# DTImp.net
KiCad netlist of a schematic drawn in Altium Designer
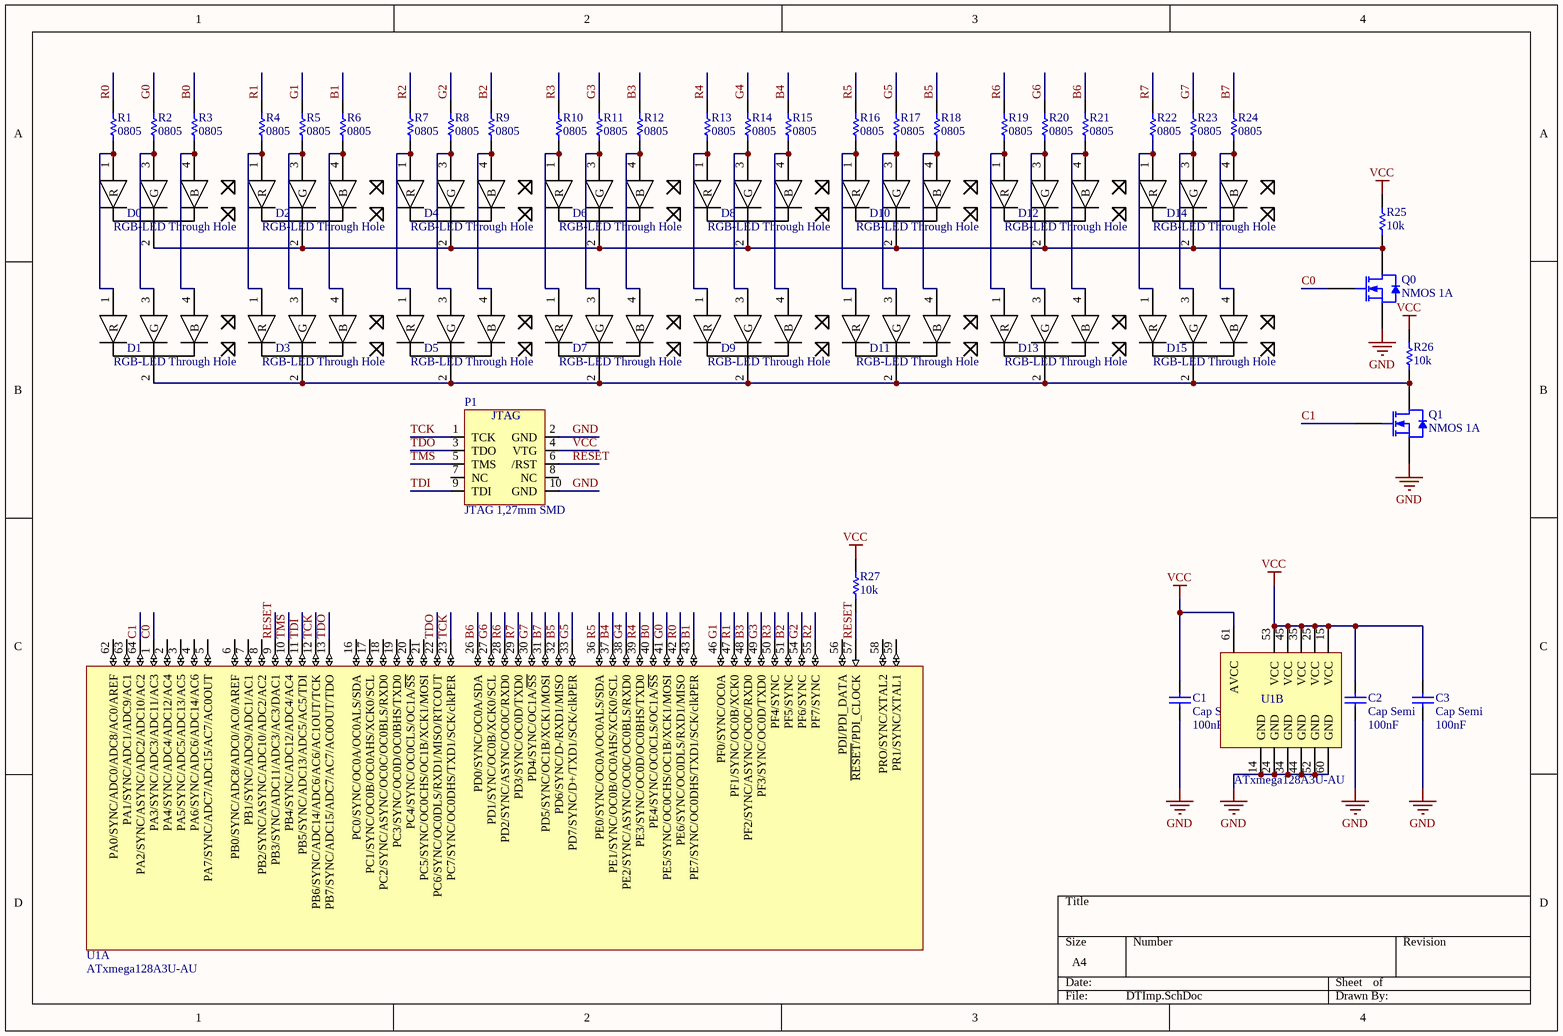
[diagram p0: DTImp.SchDoc]

(export (version "E")
  (design (tool "Eeschema 10.0.6"))
  (components
    (comp (ref "C1")
      (value "Cap Semi")
      (footprint "C1206")
      (description "Capacitor (Semiconductor SIM Model)")
      (fields (field (name "ALTIUM_VALUE") "100nF") (field (name "PUBLISHER") "Altium Limited"))
      (libsource (lib "Miscellaneous Devices") (part "Cap Semi"))
    )
    (comp (ref "C2")
      (value "Cap Semi")
      (footprint "C1206")
      (description "Capacitor (Semiconductor SIM Model)")
      (fields (field (name "ALTIUM_VALUE") "100nF") (field (name "PUBLISHER") "Altium Limited"))
      (libsource (lib "Miscellaneous Devices") (part "Cap Semi"))
    )
    (comp (ref "C3")
      (value "Cap Semi")
      (footprint "C1206")
      (description "Capacitor (Semiconductor SIM Model)")
      (fields (field (name "ALTIUM_VALUE") "100nF") (field (name "PUBLISHER") "Altium Limited"))
      (libsource (lib "Miscellaneous Devices") (part "Cap Semi"))
    )
    (comp (ref "D0")
      (value "RGB-LED Through Hole")
      (footprint "RGB-LED Through Hole")
      (libsource (lib "oystesm") (part "RGB-LED Through Hole"))
    )
    (comp (ref "D1")
      (value "RGB-LED Through Hole")
      (footprint "RGB-LED Through Hole")
      (libsource (lib "oystesm") (part "RGB-LED Through Hole"))
    )
    (comp (ref "D2")
      (value "RGB-LED Through Hole")
      (footprint "RGB-LED Through Hole")
      (libsource (lib "oystesm") (part "RGB-LED Through Hole"))
    )
    (comp (ref "D3")
      (value "RGB-LED Through Hole")
      (footprint "RGB-LED Through Hole")
      (libsource (lib "oystesm") (part "RGB-LED Through Hole"))
    )
    (comp (ref "D4")
      (value "RGB-LED Through Hole")
      (footprint "RGB-LED Through Hole")
      (libsource (lib "oystesm") (part "RGB-LED Through Hole"))
    )
    (comp (ref "D5")
      (value "RGB-LED Through Hole")
      (footprint "RGB-LED Through Hole")
      (libsource (lib "oystesm") (part "RGB-LED Through Hole"))
    )
    (comp (ref "D6")
      (value "RGB-LED Through Hole")
      (footprint "RGB-LED Through Hole")
      (libsource (lib "oystesm") (part "RGB-LED Through Hole"))
    )
    (comp (ref "D7")
      (value "RGB-LED Through Hole")
      (footprint "RGB-LED Through Hole")
      (libsource (lib "oystesm") (part "RGB-LED Through Hole"))
    )
    (comp (ref "D8")
      (value "RGB-LED Through Hole")
      (footprint "RGB-LED Through Hole")
      (libsource (lib "oystesm") (part "RGB-LED Through Hole"))
    )
    (comp (ref "D9")
      (value "RGB-LED Through Hole")
      (footprint "RGB-LED Through Hole")
      (libsource (lib "oystesm") (part "RGB-LED Through Hole"))
    )
    (comp (ref "D10")
      (value "RGB-LED Through Hole")
      (footprint "RGB-LED Through Hole")
      (libsource (lib "oystesm") (part "RGB-LED Through Hole"))
    )
    (comp (ref "D11")
      (value "RGB-LED Through Hole")
      (footprint "RGB-LED Through Hole")
      (libsource (lib "oystesm") (part "RGB-LED Through Hole"))
    )
    (comp (ref "D12")
      (value "RGB-LED Through Hole")
      (footprint "RGB-LED Through Hole")
      (libsource (lib "oystesm") (part "RGB-LED Through Hole"))
    )
    (comp (ref "D13")
      (value "RGB-LED Through Hole")
      (footprint "RGB-LED Through Hole")
      (libsource (lib "oystesm") (part "RGB-LED Through Hole"))
    )
    (comp (ref "D14")
      (value "RGB-LED Through Hole")
      (footprint "RGB-LED Through Hole")
      (libsource (lib "oystesm") (part "RGB-LED Through Hole"))
    )
    (comp (ref "D15")
      (value "RGB-LED Through Hole")
      (footprint "RGB-LED Through Hole")
      (libsource (lib "oystesm") (part "RGB-LED Through Hole"))
    )
    (comp (ref "P1")
      (value "JTAG 1,27mm SMD")
      (footprint "Header 1,27mm SMD 10P")
      (libsource (lib "oystesm") (part "JTAG 1,27mm SMD"))
    )
    (comp (ref "Q0")
      (value "NMOS 1A")
      (footprint "SOT23_N")
      (description "N-channel Enhancement Mode Field-effect Transistor")
      (fields (field (name "PUBLISHER") "Altium Limited"))
      (libsource (lib "Philips Discrete MOSFET - Low Power") (part "2N7002"))
    )
    (comp (ref "Q1")
      (value "NMOS 1A")
      (footprint "SOT23_N")
      (description "N-channel Enhancement Mode Field-effect Transistor")
      (fields (field (name "PUBLISHER") "Altium Limited"))
      (libsource (lib "Philips Discrete MOSFET - Low Power") (part "2N7002"))
    )
    (comp (ref "R1")
      (value "0805")
      (footprint "ERA-0805")
      (description "0805 SMD")
      (fields (field (name "PUBLISHER") "Altium Limited"))
      (libsource (lib "Panasonic Resistor") (part "ERA6Y"))
    )
    (comp (ref "R2")
      (value "0805")
      (footprint "ERA-0805")
      (description "0805 SMD")
      (fields (field (name "PUBLISHER") "Altium Limited"))
      (libsource (lib "Panasonic Resistor") (part "ERA6Y"))
    )
    (comp (ref "R3")
      (value "0805")
      (footprint "ERA-0805")
      (description "0805 SMD")
      (fields (field (name "PUBLISHER") "Altium Limited"))
      (libsource (lib "Panasonic Resistor") (part "ERA6Y"))
    )
    (comp (ref "R4")
      (value "0805")
      (footprint "ERA-0805")
      (description "0805 SMD")
      (fields (field (name "PUBLISHER") "Altium Limited"))
      (libsource (lib "Panasonic Resistor") (part "ERA6Y"))
    )
    (comp (ref "R5")
      (value "0805")
      (footprint "ERA-0805")
      (description "0805 SMD")
      (fields (field (name "PUBLISHER") "Altium Limited"))
      (libsource (lib "Panasonic Resistor") (part "ERA6Y"))
    )
    (comp (ref "R6")
      (value "0805")
      (footprint "ERA-0805")
      (description "0805 SMD")
      (fields (field (name "PUBLISHER") "Altium Limited"))
      (libsource (lib "Panasonic Resistor") (part "ERA6Y"))
    )
    (comp (ref "R7")
      (value "0805")
      (footprint "ERA-0805")
      (description "0805 SMD")
      (fields (field (name "PUBLISHER") "Altium Limited"))
      (libsource (lib "Panasonic Resistor") (part "ERA6Y"))
    )
    (comp (ref "R8")
      (value "0805")
      (footprint "ERA-0805")
      (description "0805 SMD")
      (fields (field (name "PUBLISHER") "Altium Limited"))
      (libsource (lib "Panasonic Resistor") (part "ERA6Y"))
    )
    (comp (ref "R9")
      (value "0805")
      (footprint "ERA-0805")
      (description "0805 SMD")
      (fields (field (name "PUBLISHER") "Altium Limited"))
      (libsource (lib "Panasonic Resistor") (part "ERA6Y"))
    )
    (comp (ref "R10")
      (value "0805")
      (footprint "ERA-0805")
      (description "0805 SMD")
      (fields (field (name "PUBLISHER") "Altium Limited"))
      (libsource (lib "Panasonic Resistor") (part "ERA6Y"))
    )
    (comp (ref "R11")
      (value "0805")
      (footprint "ERA-0805")
      (description "0805 SMD")
      (fields (field (name "PUBLISHER") "Altium Limited"))
      (libsource (lib "Panasonic Resistor") (part "ERA6Y"))
    )
    (comp (ref "R12")
      (value "0805")
      (footprint "ERA-0805")
      (description "0805 SMD")
      (fields (field (name "PUBLISHER") "Altium Limited"))
      (libsource (lib "Panasonic Resistor") (part "ERA6Y"))
    )
    (comp (ref "R13")
      (value "0805")
      (footprint "ERA-0805")
      (description "0805 SMD")
      (fields (field (name "PUBLISHER") "Altium Limited"))
      (libsource (lib "Panasonic Resistor") (part "ERA6Y"))
    )
    (comp (ref "R14")
      (value "0805")
      (footprint "ERA-0805")
      (description "0805 SMD")
      (fields (field (name "PUBLISHER") "Altium Limited"))
      (libsource (lib "Panasonic Resistor") (part "ERA6Y"))
    )
    (comp (ref "R15")
      (value "0805")
      (footprint "ERA-0805")
      (description "0805 SMD")
      (fields (field (name "PUBLISHER") "Altium Limited"))
      (libsource (lib "Panasonic Resistor") (part "ERA6Y"))
    )
    (comp (ref "R16")
      (value "0805")
      (footprint "ERA-0805")
      (description "0805 SMD")
      (fields (field (name "PUBLISHER") "Altium Limited"))
      (libsource (lib "Panasonic Resistor") (part "ERA6Y"))
    )
    (comp (ref "R17")
      (value "0805")
      (footprint "ERA-0805")
      (description "0805 SMD")
      (fields (field (name "PUBLISHER") "Altium Limited"))
      (libsource (lib "Panasonic Resistor") (part "ERA6Y"))
    )
    (comp (ref "R18")
      (value "0805")
      (footprint "ERA-0805")
      (description "0805 SMD")
      (fields (field (name "PUBLISHER") "Altium Limited"))
      (libsource (lib "Panasonic Resistor") (part "ERA6Y"))
    )
    (comp (ref "R19")
      (value "0805")
      (footprint "ERA-0805")
      (description "0805 SMD")
      (fields (field (name "PUBLISHER") "Altium Limited"))
      (libsource (lib "Panasonic Resistor") (part "ERA6Y"))
    )
    (comp (ref "R20")
      (value "0805")
      (footprint "ERA-0805")
      (description "0805 SMD")
      (fields (field (name "PUBLISHER") "Altium Limited"))
      (libsource (lib "Panasonic Resistor") (part "ERA6Y"))
    )
    (comp (ref "R21")
      (value "0805")
      (footprint "ERA-0805")
      (description "0805 SMD")
      (fields (field (name "PUBLISHER") "Altium Limited"))
      (libsource (lib "Panasonic Resistor") (part "ERA6Y"))
    )
    (comp (ref "R22")
      (value "0805")
      (footprint "ERA-0805")
      (description "0805 SMD")
      (fields (field (name "PUBLISHER") "Altium Limited"))
      (libsource (lib "Panasonic Resistor") (part "ERA6Y"))
    )
    (comp (ref "R23")
      (value "0805")
      (footprint "ERA-0805")
      (description "0805 SMD")
      (fields (field (name "PUBLISHER") "Altium Limited"))
      (libsource (lib "Panasonic Resistor") (part "ERA6Y"))
    )
    (comp (ref "R24")
      (value "0805")
      (footprint "ERA-0805")
      (description "0805 SMD")
      (fields (field (name "PUBLISHER") "Altium Limited"))
      (libsource (lib "Panasonic Resistor") (part "ERA6Y"))
    )
    (comp (ref "R25")
      (value "10k")
      (footprint "ERA-0805")
      (fields (field (name "PUBLISHER") "Altium Limited"))
      (libsource (lib "Panasonic Resistor") (part "ERA6Y"))
    )
    (comp (ref "R26")
      (value "10k")
      (footprint "ERA-0805")
      (fields (field (name "PUBLISHER") "Altium Limited"))
      (libsource (lib "Panasonic Resistor") (part "ERA6Y"))
    )
    (comp (ref "R27")
      (value "10k")
      (footprint "ERA-0805")
      (description "10kOhm")
      (fields (field (name "PUBLISHER") "Altium Limited"))
      (libsource (lib "Panasonic Resistor") (part "ERA6Y"))
    )
    (comp (ref "U1")
      (value "ATxmega128A3U-AU")
      (footprint "64A_N")
      (libsource (lib "") (part "ATxmega128A3U-AU_1"))
    )
  )
  (nets
    (net (code "1") (name "/B0") (class "Default")
      (node (ref "R3") (pin "2") (pinfunction "2_2") (pintype "passive"))
      (node (ref "U1") (pin "40") (pinfunction "PE4/SYNC/OC0CLS/OC1A/~{SS}_40") (pintype "bidirectional"))
    )
    (net (code "2") (name "/B1") (class "Default")
      (node (ref "R6") (pin "2") (pinfunction "2_2") (pintype "passive"))
      (node (ref "U1") (pin "43") (pinfunction "PE7/SYNC/OC0DHS/TXD1/SCK/clkPER_43") (pintype "bidirectional"))
    )
    (net (code "3") (name "/B2") (class "Default")
      (node (ref "R9") (pin "2") (pinfunction "2_2") (pintype "passive"))
      (node (ref "U1") (pin "51") (pinfunction "PF5/SYNC_51") (pintype "bidirectional"))
    )
    (net (code "4") (name "/B3") (class "Default")
      (node (ref "R12") (pin "2") (pinfunction "2_2") (pintype "passive"))
      (node (ref "U1") (pin "48") (pinfunction "PF2/SYNC/ASYNC/OC0C/RXD0_48") (pintype "bidirectional"))
    )
    (net (code "5") (name "/B4") (class "Default")
      (node (ref "R15") (pin "2") (pinfunction "2_2") (pintype "passive"))
      (node (ref "U1") (pin "37") (pinfunction "PE1/SYNC/OC0B/OC0AHS/XCK0/SCL_37") (pintype "bidirectional"))
    )
    (net (code "6") (name "/B5") (class "Default")
      (node (ref "R18") (pin "2") (pinfunction "2_2") (pintype "passive"))
      (node (ref "U1") (pin "32") (pinfunction "PD6/SYNC/D-/RXD1/MISO_32") (pintype "bidirectional"))
    )
    (net (code "7") (name "/B6") (class "Default")
      (node (ref "R21") (pin "2") (pinfunction "2_2") (pintype "passive"))
      (node (ref "U1") (pin "26") (pinfunction "PD0/SYNC/OC0A/SDA_26") (pintype "bidirectional"))
    )
    (net (code "8") (name "/B7") (class "Default")
      (node (ref "R24") (pin "2") (pinfunction "2_2") (pintype "passive"))
      (node (ref "U1") (pin "31") (pinfunction "PD5/SYNC/OC1B/XCK1/MOSI_31") (pintype "bidirectional"))
    )
    (net (code "9") (name "/C0") (class "Default")
      (node (ref "Q0") (pin "1") (pinfunction "G_1") (pintype "passive"))
      (node (ref "U1") (pin "1") (pinfunction "PA3/SYNC/ADC3/ADC11/AC3_1") (pintype "bidirectional"))
    )
    (net (code "10") (name "/C1") (class "Default")
      (node (ref "Q1") (pin "1") (pinfunction "G_1") (pintype "passive"))
      (node (ref "U1") (pin "64") (pinfunction "PA2/SYNC/ASYNC/ADC2/ADC10/AC2_64") (pintype "bidirectional"))
    )
    (net (code "11") (name "/G0") (class "Default")
      (node (ref "R2") (pin "2") (pinfunction "2_2") (pintype "passive"))
      (node (ref "U1") (pin "41") (pinfunction "PE5/SYNC/OC0CHS/OC1B/XCK1/MOSI_41") (pintype "bidirectional"))
    )
    (net (code "12") (name "/G1") (class "Default")
      (node (ref "R5") (pin "2") (pinfunction "2_2") (pintype "passive"))
      (node (ref "U1") (pin "46") (pinfunction "PF0/SYNC/OC0A_46") (pintype "bidirectional"))
    )
    (net (code "13") (name "/G2") (class "Default")
      (node (ref "R8") (pin "2") (pinfunction "2_2") (pintype "passive"))
      (node (ref "U1") (pin "54") (pinfunction "PF6/SYNC_54") (pintype "bidirectional"))
    )
    (net (code "14") (name "/G3") (class "Default")
      (node (ref "R11") (pin "2") (pinfunction "2_2") (pintype "passive"))
      (node (ref "U1") (pin "49") (pinfunction "PF3/SYNC/OC0D/TXD0_49") (pintype "bidirectional"))
    )
    (net (code "15") (name "/G4") (class "Default")
      (node (ref "R14") (pin "2") (pinfunction "2_2") (pintype "passive"))
      (node (ref "U1") (pin "38") (pinfunction "PE2/SYNC/ASYNC/OC0C/OC0BLS/RXD0_38") (pintype "bidirectional"))
    )
    (net (code "16") (name "/G5") (class "Default")
      (node (ref "R17") (pin "2") (pinfunction "2_2") (pintype "passive"))
      (node (ref "U1") (pin "33") (pinfunction "PD7/SYNC/D+/TXD1/SCK/clkPER_33") (pintype "bidirectional"))
    )
    (net (code "17") (name "/G6") (class "Default")
      (node (ref "R20") (pin "2") (pinfunction "2_2") (pintype "passive"))
      (node (ref "U1") (pin "27") (pinfunction "PD1/SYNC/OC0B/XCK0/SCL_27") (pintype "bidirectional"))
    )
    (net (code "18") (name "/G7") (class "Default")
      (node (ref "R23") (pin "2") (pinfunction "2_2") (pintype "passive"))
      (node (ref "U1") (pin "30") (pinfunction "PD4/SYNC/OC1A/~{SS}_30") (pintype "bidirectional"))
    )
    (net (code "19") (name "/R0") (class "Default")
      (node (ref "R1") (pin "2") (pinfunction "2_2") (pintype "passive"))
      (node (ref "U1") (pin "42") (pinfunction "PE6/SYNC/OC0DLS/RXD1/MISO_42") (pintype "bidirectional"))
    )
    (net (code "20") (name "/R1") (class "Default")
      (node (ref "R4") (pin "2") (pinfunction "2_2") (pintype "passive"))
      (node (ref "U1") (pin "47") (pinfunction "PF1/SYNC/OC0B/XCK0_47") (pintype "bidirectional"))
    )
    (net (code "21") (name "/R2") (class "Default")
      (node (ref "R7") (pin "2") (pinfunction "2_2") (pintype "passive"))
      (node (ref "U1") (pin "55") (pinfunction "PF7/SYNC_55") (pintype "bidirectional"))
    )
    (net (code "22") (name "/R3") (class "Default")
      (node (ref "R10") (pin "2") (pinfunction "2_2") (pintype "passive"))
      (node (ref "U1") (pin "50") (pinfunction "PF4/SYNC_50") (pintype "bidirectional"))
    )
    (net (code "23") (name "/R4") (class "Default")
      (node (ref "R13") (pin "2") (pinfunction "2_2") (pintype "passive"))
      (node (ref "U1") (pin "39") (pinfunction "PE3/SYNC/OC0D/OC0BHS/TXD0_39") (pintype "bidirectional"))
    )
    (net (code "24") (name "/R5") (class "Default")
      (node (ref "R16") (pin "2") (pinfunction "2_2") (pintype "passive"))
      (node (ref "U1") (pin "36") (pinfunction "PE0/SYNC/OC0A/OC0ALS/SDA_36") (pintype "bidirectional"))
    )
    (net (code "25") (name "/R6") (class "Default")
      (node (ref "R19") (pin "2") (pinfunction "2_2") (pintype "passive"))
      (node (ref "U1") (pin "28") (pinfunction "PD2/SYNC/ASYNC/OC0C/RXD0_28") (pintype "bidirectional"))
    )
    (net (code "26") (name "/R7") (class "Default")
      (node (ref "R22") (pin "2") (pinfunction "2_2") (pintype "passive"))
      (node (ref "U1") (pin "29") (pinfunction "PD3/SYNC/OC0D/TXD0_29") (pintype "bidirectional"))
    )
    (net (code "27") (name "/RESET") (class "Default")
      (node (ref "P1") (pin "6") (pinfunction "/RST_6") (pintype "passive"))
      (node (ref "R27") (pin "2") (pinfunction "2_2") (pintype "passive"))
      (node (ref "U1") (pin "57") (pinfunction "~{RESET}/PDI_CLOCK_57") (pintype "input"))
      (node (ref "U1") (pin "9") (pinfunction "PB3/SYNC/ADC11/ADC3/AC3/DAC1_9") (pintype "bidirectional"))
    )
    (net (code "28") (name "/TCK") (class "Default")
      (node (ref "P1") (pin "1") (pinfunction "TCK_1") (pintype "passive"))
      (node (ref "U1") (pin "12") (pinfunction "PB6/SYNC/ADC14/ADC6/AC6/AC1OUT/TCK_12") (pintype "bidirectional"))
      (node (ref "U1") (pin "23") (pinfunction "PC7/SYNC/OC0DHS/TXD1/SCK/clkPER_23") (pintype "bidirectional"))
    )
    (net (code "29") (name "/TDI") (class "Default")
      (node (ref "P1") (pin "9") (pinfunction "TDI_9") (pintype "passive"))
      (node (ref "U1") (pin "11") (pinfunction "PB5/SYNC/ADC13/ADC5/AC5/TDI_11") (pintype "bidirectional"))
    )
    (net (code "30") (name "/TDO") (class "Default")
      (node (ref "P1") (pin "3") (pinfunction "TDO_3") (pintype "passive"))
      (node (ref "U1") (pin "13") (pinfunction "PB7/SYNC/ADC15/ADC7/AC7/AC0OUT/TDO_13") (pintype "bidirectional"))
      (node (ref "U1") (pin "22") (pinfunction "PC6/SYNC/OC0DLS/RXD1/MISO/RTCOUT_22") (pintype "bidirectional"))
    )
    (net (code "31") (name "/TMS") (class "Default")
      (node (ref "P1") (pin "5") (pinfunction "TMS_5") (pintype "passive"))
      (node (ref "U1") (pin "10") (pinfunction "PB4/SYNC/ADC12/ADC4/AC4_10") (pintype "bidirectional"))
    )
    (net (code "32") (name "GND") (class "Default")
      (node (ref "C1") (pin "1") (pinfunction "1_1") (pintype "passive"))
      (node (ref "C2") (pin "1") (pinfunction "1_1") (pintype "passive"))
      (node (ref "C3") (pin "1") (pinfunction "1_1") (pintype "passive"))
      (node (ref "P1") (pin "10") (pinfunction "GND_10") (pintype "passive"))
      (node (ref "P1") (pin "2") (pinfunction "GND_2") (pintype "passive"))
      (node (ref "Q0") (pin "2") (pinfunction "S_2") (pintype "passive"))
      (node (ref "Q1") (pin "2") (pinfunction "S_2") (pintype "passive"))
      (node (ref "U1") (pin "14") (pinfunction "GND_14") (pintype "power_in"))
      (node (ref "U1") (pin "24") (pinfunction "GND_24") (pintype "power_in"))
      (node (ref "U1") (pin "34") (pinfunction "GND_34") (pintype "power_in"))
      (node (ref "U1") (pin "44") (pinfunction "GND_44") (pintype "power_in"))
      (node (ref "U1") (pin "52") (pinfunction "GND_52") (pintype "power_in"))
      (node (ref "U1") (pin "60") (pinfunction "GND_60") (pintype "power_in"))
    )
    (net (code "33") (name "Net-(D0-B)") (class "Default")
      (node (ref "D0") (pin "4") (pinfunction "B_4") (pintype "passive"))
      (node (ref "D1") (pin "4") (pinfunction "B_4") (pintype "passive"))
      (node (ref "R3") (pin "1") (pinfunction "1_1") (pintype "passive"))
    )
    (net (code "34") (name "Net-(D0-C)") (class "Default")
      (node (ref "D0") (pin "2") (pinfunction "C_2") (pintype "passive"))
      (node (ref "D10") (pin "2") (pinfunction "C_2") (pintype "passive"))
      (node (ref "D12") (pin "2") (pinfunction "C_2") (pintype "passive"))
      (node (ref "D14") (pin "2") (pinfunction "C_2") (pintype "passive"))
      (node (ref "D2") (pin "2") (pinfunction "C_2") (pintype "passive"))
      (node (ref "D4") (pin "2") (pinfunction "C_2") (pintype "passive"))
      (node (ref "D6") (pin "2") (pinfunction "C_2") (pintype "passive"))
      (node (ref "D8") (pin "2") (pinfunction "C_2") (pintype "passive"))
      (node (ref "Q0") (pin "3") (pinfunction "D_3") (pintype "passive"))
      (node (ref "R25") (pin "1") (pinfunction "1_1") (pintype "passive"))
    )
    (net (code "35") (name "Net-(D0-G)") (class "Default")
      (node (ref "D0") (pin "3") (pinfunction "G_3") (pintype "passive"))
      (node (ref "D1") (pin "3") (pinfunction "G_3") (pintype "passive"))
      (node (ref "R2") (pin "1") (pinfunction "1_1") (pintype "passive"))
    )
    (net (code "36") (name "Net-(D0-R)") (class "Default")
      (node (ref "D0") (pin "1") (pinfunction "R_1") (pintype "passive"))
      (node (ref "D1") (pin "1") (pinfunction "R_1") (pintype "passive"))
      (node (ref "R1") (pin "1") (pinfunction "1_1") (pintype "passive"))
    )
    (net (code "37") (name "Net-(D1-C)") (class "Default")
      (node (ref "D1") (pin "2") (pinfunction "C_2") (pintype "passive"))
      (node (ref "D11") (pin "2") (pinfunction "C_2") (pintype "passive"))
      (node (ref "D13") (pin "2") (pinfunction "C_2") (pintype "passive"))
      (node (ref "D15") (pin "2") (pinfunction "C_2") (pintype "passive"))
      (node (ref "D3") (pin "2") (pinfunction "C_2") (pintype "passive"))
      (node (ref "D5") (pin "2") (pinfunction "C_2") (pintype "passive"))
      (node (ref "D7") (pin "2") (pinfunction "C_2") (pintype "passive"))
      (node (ref "D9") (pin "2") (pinfunction "C_2") (pintype "passive"))
      (node (ref "Q1") (pin "3") (pinfunction "D_3") (pintype "passive"))
      (node (ref "R26") (pin "1") (pinfunction "1_1") (pintype "passive"))
    )
    (net (code "38") (name "Net-(D2-B)") (class "Default")
      (node (ref "D2") (pin "4") (pinfunction "B_4") (pintype "passive"))
      (node (ref "D3") (pin "4") (pinfunction "B_4") (pintype "passive"))
      (node (ref "R6") (pin "1") (pinfunction "1_1") (pintype "passive"))
    )
    (net (code "39") (name "Net-(D2-G)") (class "Default")
      (node (ref "D2") (pin "3") (pinfunction "G_3") (pintype "passive"))
      (node (ref "D3") (pin "3") (pinfunction "G_3") (pintype "passive"))
      (node (ref "R5") (pin "1") (pinfunction "1_1") (pintype "passive"))
    )
    (net (code "40") (name "Net-(D2-R)") (class "Default")
      (node (ref "D2") (pin "1") (pinfunction "R_1") (pintype "passive"))
      (node (ref "D3") (pin "1") (pinfunction "R_1") (pintype "passive"))
      (node (ref "R4") (pin "1") (pinfunction "1_1") (pintype "passive"))
    )
    (net (code "41") (name "Net-(D4-B)") (class "Default")
      (node (ref "D4") (pin "4") (pinfunction "B_4") (pintype "passive"))
      (node (ref "D5") (pin "4") (pinfunction "B_4") (pintype "passive"))
      (node (ref "R9") (pin "1") (pinfunction "1_1") (pintype "passive"))
    )
    (net (code "42") (name "Net-(D4-G)") (class "Default")
      (node (ref "D4") (pin "3") (pinfunction "G_3") (pintype "passive"))
      (node (ref "D5") (pin "3") (pinfunction "G_3") (pintype "passive"))
      (node (ref "R8") (pin "1") (pinfunction "1_1") (pintype "passive"))
    )
    (net (code "43") (name "Net-(D4-R)") (class "Default")
      (node (ref "D4") (pin "1") (pinfunction "R_1") (pintype "passive"))
      (node (ref "D5") (pin "1") (pinfunction "R_1") (pintype "passive"))
      (node (ref "R7") (pin "1") (pinfunction "1_1") (pintype "passive"))
    )
    (net (code "44") (name "Net-(D6-B)") (class "Default")
      (node (ref "D6") (pin "4") (pinfunction "B_4") (pintype "passive"))
      (node (ref "D7") (pin "4") (pinfunction "B_4") (pintype "passive"))
      (node (ref "R12") (pin "1") (pinfunction "1_1") (pintype "passive"))
    )
    (net (code "45") (name "Net-(D6-G)") (class "Default")
      (node (ref "D6") (pin "3") (pinfunction "G_3") (pintype "passive"))
      (node (ref "D7") (pin "3") (pinfunction "G_3") (pintype "passive"))
      (node (ref "R11") (pin "1") (pinfunction "1_1") (pintype "passive"))
    )
    (net (code "46") (name "Net-(D6-R)") (class "Default")
      (node (ref "D6") (pin "1") (pinfunction "R_1") (pintype "passive"))
      (node (ref "D7") (pin "1") (pinfunction "R_1") (pintype "passive"))
      (node (ref "R10") (pin "1") (pinfunction "1_1") (pintype "passive"))
    )
    (net (code "47") (name "Net-(D8-B)") (class "Default")
      (node (ref "D8") (pin "4") (pinfunction "B_4") (pintype "passive"))
      (node (ref "D9") (pin "4") (pinfunction "B_4") (pintype "passive"))
      (node (ref "R15") (pin "1") (pinfunction "1_1") (pintype "passive"))
    )
    (net (code "48") (name "Net-(D8-G)") (class "Default")
      (node (ref "D8") (pin "3") (pinfunction "G_3") (pintype "passive"))
      (node (ref "D9") (pin "3") (pinfunction "G_3") (pintype "passive"))
      (node (ref "R14") (pin "1") (pinfunction "1_1") (pintype "passive"))
    )
    (net (code "49") (name "Net-(D8-R)") (class "Default")
      (node (ref "D8") (pin "1") (pinfunction "R_1") (pintype "passive"))
      (node (ref "D9") (pin "1") (pinfunction "R_1") (pintype "passive"))
      (node (ref "R13") (pin "1") (pinfunction "1_1") (pintype "passive"))
    )
    (net (code "50") (name "Net-(D10-B)") (class "Default")
      (node (ref "D10") (pin "4") (pinfunction "B_4") (pintype "passive"))
      (node (ref "D11") (pin "4") (pinfunction "B_4") (pintype "passive"))
      (node (ref "R18") (pin "1") (pinfunction "1_1") (pintype "passive"))
    )
    (net (code "51") (name "Net-(D10-G)") (class "Default")
      (node (ref "D10") (pin "3") (pinfunction "G_3") (pintype "passive"))
      (node (ref "D11") (pin "3") (pinfunction "G_3") (pintype "passive"))
      (node (ref "R17") (pin "1") (pinfunction "1_1") (pintype "passive"))
    )
    (net (code "52") (name "Net-(D10-R)") (class "Default")
      (node (ref "D10") (pin "1") (pinfunction "R_1") (pintype "passive"))
      (node (ref "D11") (pin "1") (pinfunction "R_1") (pintype "passive"))
      (node (ref "R16") (pin "1") (pinfunction "1_1") (pintype "passive"))
    )
    (net (code "53") (name "Net-(D12-B)") (class "Default")
      (node (ref "D12") (pin "4") (pinfunction "B_4") (pintype "passive"))
      (node (ref "D13") (pin "4") (pinfunction "B_4") (pintype "passive"))
      (node (ref "R21") (pin "1") (pinfunction "1_1") (pintype "passive"))
    )
    (net (code "54") (name "Net-(D12-G)") (class "Default")
      (node (ref "D12") (pin "3") (pinfunction "G_3") (pintype "passive"))
      (node (ref "D13") (pin "3") (pinfunction "G_3") (pintype "passive"))
      (node (ref "R20") (pin "1") (pinfunction "1_1") (pintype "passive"))
    )
    (net (code "55") (name "Net-(D12-R)") (class "Default")
      (node (ref "D12") (pin "1") (pinfunction "R_1") (pintype "passive"))
      (node (ref "D13") (pin "1") (pinfunction "R_1") (pintype "passive"))
      (node (ref "R19") (pin "1") (pinfunction "1_1") (pintype "passive"))
    )
    (net (code "56") (name "Net-(D14-B)") (class "Default")
      (node (ref "D14") (pin "4") (pinfunction "B_4") (pintype "passive"))
      (node (ref "D15") (pin "4") (pinfunction "B_4") (pintype "passive"))
      (node (ref "R24") (pin "1") (pinfunction "1_1") (pintype "passive"))
    )
    (net (code "57") (name "Net-(D14-G)") (class "Default")
      (node (ref "D14") (pin "3") (pinfunction "G_3") (pintype "passive"))
      (node (ref "D15") (pin "3") (pinfunction "G_3") (pintype "passive"))
      (node (ref "R23") (pin "1") (pinfunction "1_1") (pintype "passive"))
    )
    (net (code "58") (name "Net-(D14-R)") (class "Default")
      (node (ref "D14") (pin "1") (pinfunction "R_1") (pintype "passive"))
      (node (ref "D15") (pin "1") (pinfunction "R_1") (pintype "passive"))
      (node (ref "R22") (pin "1") (pinfunction "1_1") (pintype "passive"))
    )
    (net (code "59") (name "VCC") (class "Default")
      (node (ref "C1") (pin "2") (pinfunction "2_2") (pintype "passive"))
      (node (ref "C2") (pin "2") (pinfunction "2_2") (pintype "passive"))
      (node (ref "C3") (pin "2") (pinfunction "2_2") (pintype "passive"))
      (node (ref "P1") (pin "4") (pinfunction "VTG_4") (pintype "passive"))
      (node (ref "R25") (pin "2") (pinfunction "2_2") (pintype "passive"))
      (node (ref "R26") (pin "2") (pinfunction "2_2") (pintype "passive"))
      (node (ref "R27") (pin "1") (pinfunction "1_1") (pintype "passive"))
      (node (ref "U1") (pin "15") (pinfunction "VCC_15") (pintype "power_in"))
      (node (ref "U1") (pin "25") (pinfunction "VCC_25") (pintype "power_in"))
      (node (ref "U1") (pin "35") (pinfunction "VCC_35") (pintype "power_in"))
      (node (ref "U1") (pin "45") (pinfunction "VCC_45") (pintype "power_in"))
      (node (ref "U1") (pin "53") (pinfunction "VCC_53") (pintype "power_in"))
      (node (ref "U1") (pin "61") (pinfunction "AVCC_61") (pintype "power_in"))
    )
    (net (code "60") (name "unconnected-(P1-NC-Pad7)") (class "Default")
      (node (ref "P1") (pin "7") (pinfunction "NC_7") (pintype "passive"))
    )
    (net (code "61") (name "unconnected-(P1-NC-Pad8)") (class "Default")
      (node (ref "P1") (pin "8") (pinfunction "NC_8") (pintype "passive"))
    )
    (net (code "62") (name "unconnected-(U1A-PA0{slash}SYNC{slash}ADC0{slash}ADC8{slash}AC0{slash}AREF-Pad62)") (class "Default")
      (node (ref "U1") (pin "62") (pinfunction "PA0/SYNC/ADC0/ADC8/AC0/AREF_62") (pintype "bidirectional"))
    )
    (net (code "63") (name "unconnected-(U1A-PA1{slash}SYNC{slash}ADC1{slash}ADC9{slash}AC1-Pad63)") (class "Default")
      (node (ref "U1") (pin "63") (pinfunction "PA1/SYNC/ADC1/ADC9/AC1_63") (pintype "bidirectional"))
    )
    (net (code "64") (name "unconnected-(U1A-PA4{slash}SYNC{slash}ADC4{slash}ADC12{slash}AC4-Pad2)") (class "Default")
      (node (ref "U1") (pin "2") (pinfunction "PA4/SYNC/ADC4/ADC12/AC4_2") (pintype "bidirectional"))
    )
    (net (code "65") (name "unconnected-(U1A-PA5{slash}SYNC{slash}ADC5{slash}ADC13{slash}AC5-Pad3)") (class "Default")
      (node (ref "U1") (pin "3") (pinfunction "PA5/SYNC/ADC5/ADC13/AC5_3") (pintype "bidirectional"))
    )
    (net (code "66") (name "unconnected-(U1A-PA6{slash}SYNC{slash}ADC6{slash}ADC14{slash}AC6-Pad4)") (class "Default")
      (node (ref "U1") (pin "4") (pinfunction "PA6/SYNC/ADC6/ADC14/AC6_4") (pintype "bidirectional"))
    )
    (net (code "67") (name "unconnected-(U1A-PA7{slash}SYNC{slash}ADC7{slash}ADC15{slash}AC7{slash}AC0OUT-Pad5)") (class "Default")
      (node (ref "U1") (pin "5") (pinfunction "PA7/SYNC/ADC7/ADC15/AC7/AC0OUT_5") (pintype "bidirectional"))
    )
    (net (code "68") (name "unconnected-(U1A-PB0{slash}SYNC{slash}ADC8{slash}ADC0{slash}AC0{slash}AREF-Pad6)") (class "Default")
      (node (ref "U1") (pin "6") (pinfunction "PB0/SYNC/ADC8/ADC0/AC0/AREF_6") (pintype "bidirectional"))
    )
    (net (code "69") (name "unconnected-(U1A-PB1{slash}SYNC{slash}ADC9{slash}ADC1{slash}AC1-Pad7)") (class "Default")
      (node (ref "U1") (pin "7") (pinfunction "PB1/SYNC/ADC9/ADC1/AC1_7") (pintype "bidirectional"))
    )
    (net (code "70") (name "unconnected-(U1A-PB2{slash}SYNC{slash}ASYNC{slash}ADC10{slash}ADC2{slash}AC2-Pad8)") (class "Default")
      (node (ref "U1") (pin "8") (pinfunction "PB2/SYNC/ASYNC/ADC10/ADC2/AC2_8") (pintype "bidirectional"))
    )
    (net (code "71") (name "unconnected-(U1A-PC0{slash}SYNC{slash}OC0A{slash}OC0ALS{slash}SDA-Pad16)") (class "Default")
      (node (ref "U1") (pin "16") (pinfunction "PC0/SYNC/OC0A/OC0ALS/SDA_16") (pintype "bidirectional"))
    )
    (net (code "72") (name "unconnected-(U1A-PC1{slash}SYNC{slash}OC0B{slash}OC0AHS{slash}XCK0{slash}SCL-Pad17)") (class "Default")
      (node (ref "U1") (pin "17") (pinfunction "PC1/SYNC/OC0B/OC0AHS/XCK0/SCL_17") (pintype "bidirectional"))
    )
    (net (code "73") (name "unconnected-(U1A-PC2{slash}SYNC{slash}ASYNC{slash}OC0C{slash}OC0BLS{slash}RXD0-Pad18)") (class "Default")
      (node (ref "U1") (pin "18") (pinfunction "PC2/SYNC/ASYNC/OC0C/OC0BLS/RXD0_18") (pintype "bidirectional"))
    )
    (net (code "74") (name "unconnected-(U1A-PC3{slash}SYNC{slash}OC0D{slash}OC0BHS{slash}TXD0-Pad19)") (class "Default")
      (node (ref "U1") (pin "19") (pinfunction "PC3/SYNC/OC0D/OC0BHS/TXD0_19") (pintype "bidirectional"))
    )
    (net (code "75") (name "unconnected-(U1A-PC4{slash}SYNC{slash}OC0CLS{slash}OC1A{slash}~{SS}-Pad20)") (class "Default")
      (node (ref "U1") (pin "20") (pinfunction "PC4/SYNC/OC0CLS/OC1A/~{SS}_20") (pintype "bidirectional"))
    )
    (net (code "76") (name "unconnected-(U1A-PC5{slash}SYNC{slash}OC0CHS{slash}OC1B{slash}XCK1{slash}MOSI-Pad21)") (class "Default")
      (node (ref "U1") (pin "21") (pinfunction "PC5/SYNC/OC0CHS/OC1B/XCK1/MOSI_21") (pintype "bidirectional"))
    )
    (net (code "77") (name "unconnected-(U1A-PDI{slash}PDI_DATA-Pad56)") (class "Default")
      (node (ref "U1") (pin "56") (pinfunction "PDI/PDI_DATA_56") (pintype "bidirectional"))
    )
    (net (code "78") (name "unconnected-(U1A-PR1{slash}SYNC{slash}XTAL1-Pad59)") (class "Default")
      (node (ref "U1") (pin "59") (pinfunction "PR1/SYNC/XTAL1_59") (pintype "bidirectional"))
    )
    (net (code "79") (name "unconnected-(U1A-PRO{slash}SYNC{slash}XTAL2-Pad58)") (class "Default")
      (node (ref "U1") (pin "58") (pinfunction "PRO/SYNC/XTAL2_58") (pintype "bidirectional"))
    )
  )
)
